# GENERADORA_V1_5.net
KiCad netlist of a schematic drawn in Altium Designer
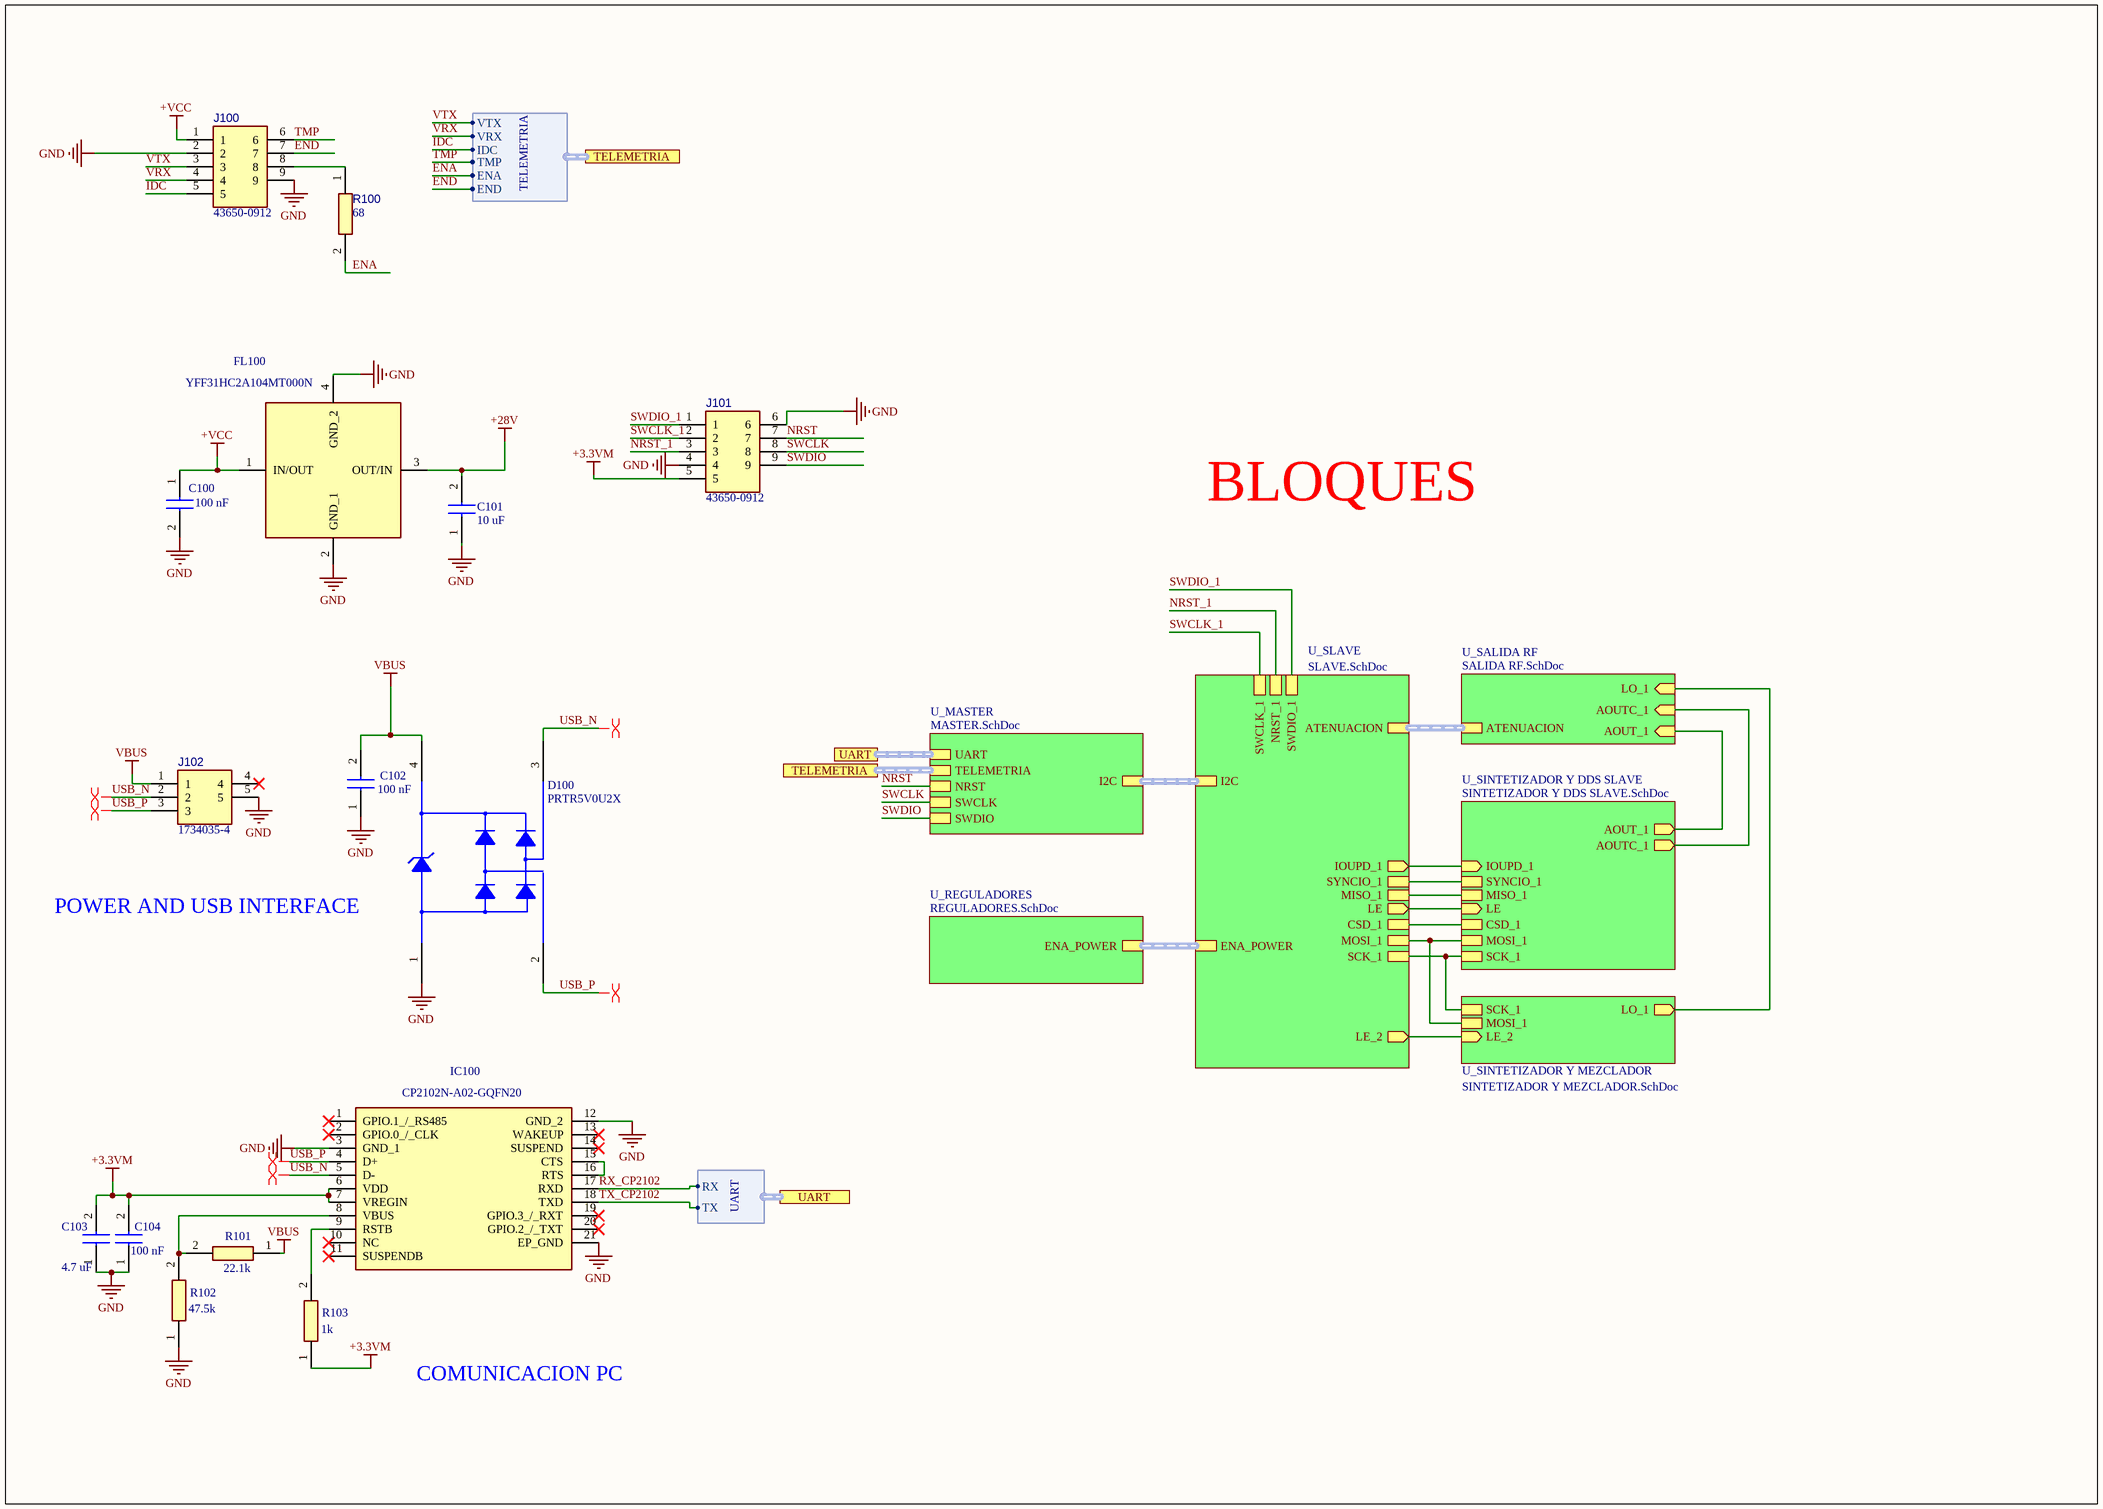
[diagram p0: GENERADORA V1.5.SchDoc]

(export (version "E")
  (design (tool "Eeschema 10.0.6"))
  (components
    (comp (ref "C100")
      (value "100 nF")
      (footprint "SamacSys:CAPC3216X94N")
      (description "Capacitor")
      (fields
        (field (name "MANUFACTURER_PART_NUMBER") "KAM31BR81H103KT")
        (field (name "MOUSER PART NUMBER") "581-KAM31BR81H103KT")
      )
      (libsource (lib "LIBRERIA_GEN_V2.0") (part "KAM31BR81H103KT"))
    )
    (comp (ref "C101")
      (value "10 uF")
      (footprint "SamacSys:CAPC3216X94N")
      (description "Capacitor")
      (fields
        (field (name "MANUFACTURER_PART_NUMBER") "KAM31BR81H103KT")
        (field (name "MOUSER PART NUMBER") "581-KAM31BR81H103KT")
      )
      (libsource (lib "LIBRERIA_GEN_V2.0") (part "KAM31BR81H103KT"))
    )
    (comp (ref "C102")
      (value "100 nF")
      (footprint "SamacSys:CAPC3216X94N")
      (description "Capacitor")
      (fields
        (field (name "MANUFACTURER_PART_NUMBER") "KAM31BR81H103KT")
        (field (name "MOUSER PART NUMBER") "581-KAM31BR81H103KT")
      )
      (libsource (lib "LIBRERIA_GEN_V2.0") (part "KAM31BR81H103KT"))
    )
    (comp (ref "C103")
      (value "4.7 uF")
      (footprint "SamacSys:C0603")
      (description "Capacitor")
      (fields (field (name "MANUFACTURER_PART_NUMBER") "C0603H470J5GACTU"))
      (libsource (lib "LIBRERIA_GEN_V2.0") (part "C0603H470J5GACTU"))
    )
    (comp (ref "C104")
      (value "100 nF")
      (footprint "SamacSys:C0603")
      (description "Capacitor")
      (fields (field (name "MANUFACTURER_PART_NUMBER") "C0603H470J5GACTU"))
      (libsource (lib "LIBRERIA_GEN_V2.0") (part "C0603H470J5GACTU"))
    )
    (comp (ref "D100")
      (value "PRTR5V0U2X")
      (footprint "AP4-00001")
      (description "Double rail-to-rail USB ESD protection diode")
      (fields (field (name "MANUFACTURER") "Philips"))
      (libsource (lib "SAM4S_Xplained_Pro") (part "PRTR5V0U2X"))
    )
    (comp (ref "FL100")
      (value "YFF31HC2A104MT000N")
      (footprint "SamacSys:YFF31HC2A104MT000N")
      (description "Filter")
      (fields (field (name "MOUSER PART NUMBER") "810-YFF31HC2A104MTHN"))
      (libsource (lib "LIBRERIA_GEN_V2.0") (part "YFF31HC2A104MT000N"))
    )
    (comp (ref "IC100")
      (value "CP2102N-A02-GQFN20")
      (footprint "SamacSys:CP2102NA02GQFN20")
      (description "Integrated Circuit")
      (fields (field (name "MOUSER PART NUMBER") "634-CP2102NA02GQFN20"))
      (libsource (lib "LIBRERIA_GEN_V2.0") (part "CP2102N-A02-GQFN20"))
    )
    (comp (ref "J100")
      (value "43650-0912")
      (footprint "SamacSys:43650-09(12,13,14)")
      (description "Connector")
      (fields (field (name "MOUSER PART NUMBER") "538-43650-0912"))
      (libsource (lib "*") (part "43650-0912"))
    )
    (comp (ref "J101")
      (value "43650-0912")
      (footprint "SamacSys:43650-09(12,13,14)")
      (description "Connector")
      (fields (field (name "MOUSER PART NUMBER") "538-43650-0912"))
      (libsource (lib "*") (part "43650-0912"))
    )
    (comp (ref "J102")
      (value "1734035-4")
      (footprint "SamacSys:1734035-2USB")
      (description "Connector")
      (fields (field (name "MOUSER PART NUMBER") "571-1734035-4"))
      (libsource (lib "SamacSys") (part "1734035-4"))
    )
    (comp (ref "R100")
      (value "68")
      (footprint "SamacSys:RESC1608X55N")
      (description "Resistor")
      (fields
        (field (name "MANUFACTURER_PART_NUMBER") "CR0603-FX-1431ELF")
        (field (name "MOUSER PART NUMBER") "652-CR0603FX-1431ELF")
      )
      (libsource (lib "*") (part "CR0603-FX-1431ELF"))
    )
    (comp (ref "R101")
      (value "22.1k")
      (footprint "SamacSys:RESC1608X55N")
      (description "Resistor")
      (fields
        (field (name "MANUFACTURER_PART_NUMBER") "CR0603-FX-1431ELF")
        (field (name "MOUSER PART NUMBER") "652-CR0603FX-1431ELF")
      )
      (libsource (lib "") (part "CR0603-FX-1431ELF_1"))
    )
    (comp (ref "R102")
      (value "47.5k")
      (footprint "SamacSys:RESC1608X55N")
      (description "Resistor")
      (fields
        (field (name "MANUFACTURER_PART_NUMBER") "CR0603-FX-1431ELF")
        (field (name "MOUSER PART NUMBER") "652-CR0603FX-1431ELF")
      )
      (libsource (lib "LIBRERIA_GEN_V2.0") (part "CR0603-FX-1431ELF"))
    )
    (comp (ref "R103")
      (value "1k")
      (footprint "SamacSys:RESC1608X55N")
      (description "Resistor")
      (fields
        (field (name "MANUFACTURER_PART_NUMBER") "CR0603-FX-1431ELF")
        (field (name "MOUSER PART NUMBER") "652-CR0603FX-1431ELF")
      )
      (libsource (lib "LIBRERIA_GEN_V2.0") (part "CR0603-FX-1431ELF"))
    )
  )
  (nets
    (net (code "4") (name "+3.3VM") (class "Default")
      (node (ref "C103") (pin "2") (pinfunction "2_2") (pintype "passive"))
      (node (ref "C104") (pin "2") (pinfunction "2_2") (pintype "passive"))
      (node (ref "IC100") (pin "6") (pinfunction "VDD_6") (pintype "passive"))
      (node (ref "IC100") (pin "7") (pinfunction "VREGIN_7") (pintype "passive"))
      (node (ref "J101") (pin "5") (pinfunction "5_5") (pintype "passive"))
      (node (ref "R103") (pin "1") (pinfunction "1_1") (pintype "passive"))
    )
    (net (code "5") (name "+28V") (class "Default")
      (node (ref "C101") (pin "2") (pinfunction "2_2") (pintype "passive"))
      (node (ref "FL100") (pin "3") (pinfunction "OUT/IN_3") (pintype "passive"))
    )
    (net (code "6") (name "+VCC") (class "Default")
      (node (ref "C100") (pin "1") (pinfunction "1_1") (pintype "passive"))
      (node (ref "FL100") (pin "1") (pinfunction "IN/OUT_1") (pintype "passive"))
      (node (ref "J100") (pin "1") (pinfunction "1_1") (pintype "passive"))
    )
    (net (code "11") (name "/ENA") (class "Default")
      (node (ref "R100") (pin "2") (pinfunction "2_2") (pintype "passive"))
    )
    (net (code "13") (name "/END") (class "Default")
      (node (ref "J100") (pin "7") (pinfunction "7_7") (pintype "passive"))
    )
    (net (code "15") (name "/IDC") (class "Default")
      (node (ref "J100") (pin "5") (pinfunction "5_5") (pintype "passive"))
    )
    (net (code "22") (name "/NRST") (class "Default")
      (node (ref "J101") (pin "7") (pinfunction "7_7") (pintype "passive"))
    )
    (net (code "23") (name "/NRST_1") (class "Default")
      (node (ref "J101") (pin "3") (pinfunction "3_3") (pintype "passive"))
    )
    (net (code "24") (name "/RX_CP2102") (class "Default")
      (node (ref "IC100") (pin "17") (pinfunction "RXD_17") (pintype "passive"))
    )
    (net (code "26") (name "/SWCLK") (class "Default")
      (node (ref "J101") (pin "8") (pinfunction "8_8") (pintype "passive"))
    )
    (net (code "27") (name "/SWCLK_1") (class "Default")
      (node (ref "J101") (pin "2") (pinfunction "2_2") (pintype "passive"))
    )
    (net (code "28") (name "/SWDIO") (class "Default")
      (node (ref "J101") (pin "9") (pinfunction "9_9") (pintype "passive"))
    )
    (net (code "29") (name "/SWDIO_1") (class "Default")
      (node (ref "J101") (pin "1") (pinfunction "1_1") (pintype "passive"))
    )
    (net (code "31") (name "/TMP") (class "Default")
      (node (ref "J100") (pin "6") (pinfunction "6_6") (pintype "passive"))
    )
    (net (code "32") (name "/TX_CP2102") (class "Default")
      (node (ref "IC100") (pin "18") (pinfunction "TXD_18") (pintype "passive"))
    )
    (net (code "34") (name "/USB_N") (class "Default")
      (node (ref "D100") (pin "3") (pinfunction "I/O_2_3") (pintype "passive"))
      (node (ref "IC100") (pin "5") (pinfunction "D-_5") (pintype "passive"))
      (node (ref "J102") (pin "2") (pinfunction "2_2") (pintype "passive"))
    )
    (net (code "35") (name "/USB_P") (class "Default")
      (node (ref "D100") (pin "2") (pinfunction "I/O_1_2") (pintype "passive"))
      (node (ref "IC100") (pin "4") (pinfunction "D+_4") (pintype "passive"))
      (node (ref "J102") (pin "3") (pinfunction "3_3") (pintype "passive"))
    )
    (net (code "36") (name "/VRX") (class "Default")
      (node (ref "J100") (pin "4") (pinfunction "4_4") (pintype "passive"))
    )
    (net (code "37") (name "/VTX") (class "Default")
      (node (ref "J100") (pin "3") (pinfunction "3_3") (pintype "passive"))
    )
    (net (code "40") (name "GND") (class "Default")
      (node (ref "C100") (pin "2") (pinfunction "2_2") (pintype "passive"))
      (node (ref "C101") (pin "1") (pinfunction "1_1") (pintype "passive"))
      (node (ref "C102") (pin "1") (pinfunction "1_1") (pintype "passive"))
      (node (ref "C103") (pin "1") (pinfunction "1_1") (pintype "passive"))
      (node (ref "C104") (pin "1") (pinfunction "1_1") (pintype "passive"))
      (node (ref "D100") (pin "1") (pinfunction "GND_1") (pintype "passive"))
      (node (ref "FL100") (pin "2") (pinfunction "GND_1_2") (pintype "passive"))
      (node (ref "FL100") (pin "4") (pinfunction "GND_2_4") (pintype "passive"))
      (node (ref "IC100") (pin "12") (pinfunction "GND_2_12") (pintype "passive"))
      (node (ref "IC100") (pin "21") (pinfunction "EP_GND_21") (pintype "passive"))
      (node (ref "IC100") (pin "3") (pinfunction "GND_1_3") (pintype "passive"))
      (node (ref "J100") (pin "2") (pinfunction "2_2") (pintype "passive"))
      (node (ref "J100") (pin "9") (pinfunction "9_9") (pintype "passive"))
      (node (ref "J101") (pin "4") (pinfunction "4_4") (pintype "passive"))
      (node (ref "J101") (pin "6") (pinfunction "6_6") (pintype "passive"))
      (node (ref "J102") (pin "5") (pinfunction "5_5") (pintype "passive"))
      (node (ref "R102") (pin "1") (pinfunction "1_1") (pintype "passive"))
    )
    (net (code "41") (name "Net-(IC100-CTS)") (class "Default")
      (node (ref "IC100") (pin "15") (pinfunction "CTS_15") (pintype "passive"))
      (node (ref "IC100") (pin "16") (pinfunction "RTS_16") (pintype "passive"))
    )
    (net (code "42") (name "Net-(IC100-RSTB)") (class "Default")
      (node (ref "IC100") (pin "9") (pinfunction "RSTB_9") (pintype "passive"))
      (node (ref "R103") (pin "2") (pinfunction "2_2") (pintype "passive"))
    )
    (net (code "43") (name "Net-(IC100-VBUS)") (class "Default")
      (node (ref "IC100") (pin "8") (pinfunction "VBUS_8") (pintype "passive"))
      (node (ref "R101") (pin "2") (pinfunction "2_2") (pintype "passive"))
      (node (ref "R102") (pin "2") (pinfunction "2_2") (pintype "passive"))
    )
    (net (code "44") (name "Net-(J100-Pad8)") (class "Default")
      (node (ref "J100") (pin "8") (pinfunction "8_8") (pintype "passive"))
      (node (ref "R100") (pin "1") (pinfunction "1_1") (pintype "passive"))
    )
    (net (code "45") (name "VBUS") (class "Default")
      (node (ref "C102") (pin "2") (pinfunction "2_2") (pintype "passive"))
      (node (ref "D100") (pin "4") (pinfunction "VCC_4") (pintype "passive"))
      (node (ref "J102") (pin "1") (pinfunction "1_1") (pintype "passive"))
      (node (ref "R101") (pin "1") (pinfunction "1_1") (pintype "passive"))
    )
    (net (code "46") (name "unconnected-(IC100-GPIO.0_{slash}_CLK-Pad2)") (class "Default")
      (node (ref "IC100") (pin "2") (pinfunction "GPIO.0_/_CLK_2") (pintype "passive+no_connect"))
    )
    (net (code "47") (name "unconnected-(IC100-GPIO.1_{slash}_RS485-Pad1)") (class "Default")
      (node (ref "IC100") (pin "1") (pinfunction "GPIO.1_/_RS485_1") (pintype "passive+no_connect"))
    )
    (net (code "48") (name "unconnected-(IC100-GPIO.2_{slash}_TXT-Pad20)") (class "Default")
      (node (ref "IC100") (pin "20") (pinfunction "GPIO.2_/_TXT_20") (pintype "passive+no_connect"))
    )
    (net (code "49") (name "unconnected-(IC100-GPIO.3_{slash}_RXT-Pad19)") (class "Default")
      (node (ref "IC100") (pin "19") (pinfunction "GPIO.3_/_RXT_19") (pintype "passive+no_connect"))
    )
    (net (code "50") (name "unconnected-(IC100-NC-Pad10)") (class "Default")
      (node (ref "IC100") (pin "10") (pinfunction "NC_10") (pintype "passive+no_connect"))
    )
    (net (code "51") (name "unconnected-(IC100-SUSPEND-Pad14)") (class "Default")
      (node (ref "IC100") (pin "14") (pinfunction "SUSPEND_14") (pintype "passive+no_connect"))
    )
    (net (code "52") (name "unconnected-(IC100-SUSPENDB-Pad11)") (class "Default")
      (node (ref "IC100") (pin "11") (pinfunction "SUSPENDB_11") (pintype "passive+no_connect"))
    )
    (net (code "53") (name "unconnected-(IC100-WAKEUP-Pad13)") (class "Default")
      (node (ref "IC100") (pin "13") (pinfunction "WAKEUP_13") (pintype "passive+no_connect"))
    )
    (net (code "54") (name "unconnected-(J102-Pad4)") (class "Default")
      (node (ref "J102") (pin "4") (pinfunction "4_4") (pintype "passive+no_connect"))
    )
  )
)
